# Wattuino-Nanite85_v10.net
KiCad netlist of a schematic drawn in EAGLE
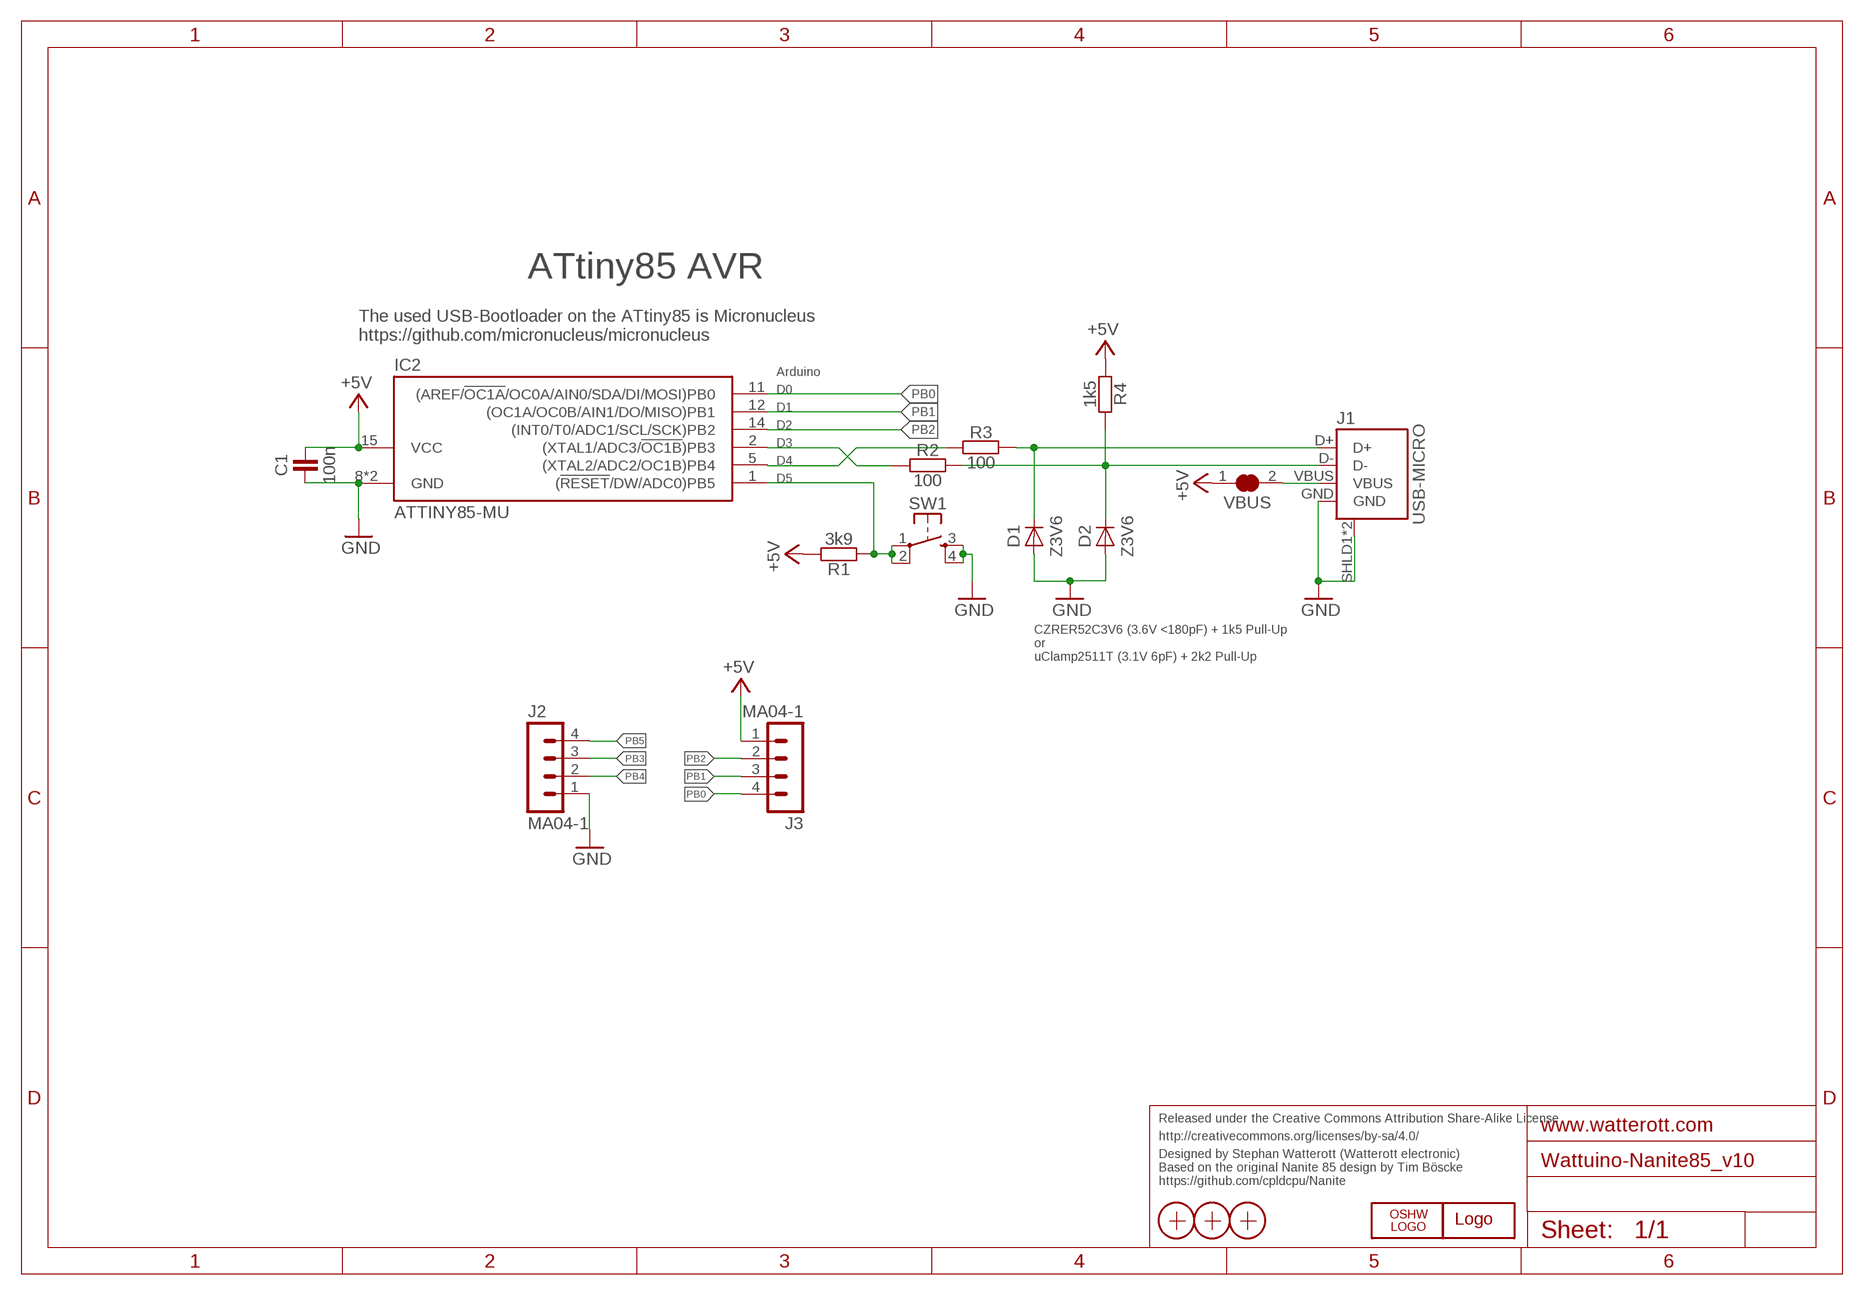
[diagram p0: schematic, sheet 1]

(export (version "E")
  (design (tool "Eeschema 10.0.6"))
  (components
    (comp (ref "C1")
      (value "100n")
      (footprint "eagle-import:C0402")
      (libsource (lib "eagle-import") (part "CAPACITOR-0402"))
    )
    (comp (ref "D1")
      (value "Z3V6")
      (footprint "eagle-import:SOD882")
      (libsource (lib "eagle-import") (part "DIODE-SOD882"))
    )
    (comp (ref "D2")
      (value "Z3V6")
      (footprint "eagle-import:SOD882")
      (libsource (lib "eagle-import") (part "DIODE-SOD882"))
    )
    (comp (ref "IC2")
      (value "ATTINY85-MU")
      (footprint "eagle-import:QFN20-PAD")
      (libsource (lib "eagle-import") (part "ATTINY85-MU"))
    )
    (comp (ref "J1")
      (value "USB-MICRO")
      (footprint "eagle-import:USB-MICRO-10103594")
      (libsource (lib "eagle-import") (part "USB-MICRO"))
    )
    (comp (ref "J2")
      (value "MA04-1")
      (footprint "eagle-import:MA04-1")
      (libsource (lib "eagle-import") (part "MA04-1"))
    )
    (comp (ref "J3")
      (value "MA04-1")
      (footprint "eagle-import:MA04-1")
      (libsource (lib "eagle-import") (part "MA04-1"))
    )
    (comp (ref "LOGO1")
      (value "LOGO-S_PLACE_S")
      (footprint "eagle-import:SPARK_TPLACE_S")
      (libsource (lib "eagle-import") (part "LOGO-S_PLACE_S"))
    )
    (comp (ref "LOGO2")
      (value "OSHW_LOGOX0070")
      (footprint "eagle-import:OSHW_6X70")
      (libsource (lib "eagle-import") (part "OSHW_LOGOX0070"))
    )
    (comp (ref "R1")
      (value "3k9")
      (footprint "eagle-import:C0402")
      (libsource (lib "eagle-import") (part "RESISTOR-0402"))
    )
    (comp (ref "R2")
      (value "100")
      (footprint "eagle-import:C0402")
      (libsource (lib "eagle-import") (part "RESISTOR-0402"))
    )
    (comp (ref "R3")
      (value "100")
      (footprint "eagle-import:C0402")
      (libsource (lib "eagle-import") (part "RESISTOR-0402"))
    )
    (comp (ref "R4")
      (value "1k5")
      (footprint "eagle-import:C0402")
      (libsource (lib "eagle-import") (part "RESISTOR-0402"))
    )
    (comp (ref "SW1")
      (value "SW-TACTILE-PTS840P")
      (footprint "eagle-import:SW_PTS840P")
      (libsource (lib "eagle-import") (part "SW-TACTILE-PTS840P"))
    )
    (comp (ref "VBUS")
      (value "JUMPER2-0603-NC")
      (footprint "eagle-import:JUMPER2-0603_NC")
      (libsource (lib "eagle-import") (part "JUMPER2-0603-NC"))
    )
    (comp (ref "X1")
      (value "PASSER-07")
      (footprint "eagle-import:PASSER_07MM")
      (libsource (lib "eagle-import") (part "PASSER-07"))
    )
    (comp (ref "X2")
      (value "PASSER-07")
      (footprint "eagle-import:PASSER_07MM")
      (libsource (lib "eagle-import") (part "PASSER-07"))
    )
    (comp (ref "X3")
      (value "PASSER-07")
      (footprint "eagle-import:PASSER_07MM")
      (libsource (lib "eagle-import") (part "PASSER-07"))
    )
  )
  (nets
    (net (code "1") (name "+5V") (class "Default")
      (node (ref "C1") (pin "2") (pinfunction "2_2") (pintype "passive"))
      (node (ref "IC2") (pin "15") (pinfunction "VCC_15") (pintype "power_in"))
      (node (ref "J3") (pin "1") (pinfunction "1_1") (pintype "passive"))
      (node (ref "R1") (pin "2") (pinfunction "2_2") (pintype "passive"))
      (node (ref "R4") (pin "1") (pinfunction "1_1") (pintype "passive"))
      (node (ref "VBUS") (pin "1") (pinfunction "1_1") (pintype "passive"))
    )
    (net (code "2") (name "GND") (class "Default")
      (node (ref "C1") (pin "1") (pinfunction "1_1") (pintype "passive"))
      (node (ref "D1") (pin "A") (pinfunction "A_A") (pintype "passive"))
      (node (ref "D2") (pin "A") (pinfunction "A_A") (pintype "passive"))
      (node (ref "IC2") (pin "8") (pinfunction "GND_8") (pintype "power_in"))
      (node (ref "IC2") (pin "TP") (pinfunction "GND_TP") (pintype "power_in"))
      (node (ref "J1") (pin "GND") (pinfunction "GND_GND") (pintype "power_in"))
      (node (ref "J1") (pin "SHLD1") (pinfunction "SHIELD_SHLD1") (pintype "passive"))
      (node (ref "J1") (pin "SHLD2") (pinfunction "SHIELD_SHLD2") (pintype "passive"))
      (node (ref "J2") (pin "1") (pinfunction "1_1") (pintype "passive"))
      (node (ref "SW1") (pin "3") (pinfunction "S1_3") (pintype "passive"))
      (node (ref "SW1") (pin "4") (pinfunction "S2_4") (pintype "passive"))
    )
    (net (code "3") (name "Net-(D1-PadC)") (class "Default")
      (node (ref "D1") (pin "C") (pinfunction "C_C") (pintype "passive"))
      (node (ref "J1") (pin "D+") (pinfunction "D+_D+") (pintype "bidirectional"))
      (node (ref "R3") (pin "2") (pinfunction "2_2") (pintype "passive"))
    )
    (net (code "4") (name "Net-(D2-PadC)") (class "Default")
      (node (ref "D2") (pin "C") (pinfunction "C_C") (pintype "passive"))
      (node (ref "J1") (pin "D-") (pinfunction "D-_D-") (pintype "bidirectional"))
      (node (ref "R2") (pin "2") (pinfunction "2_2") (pintype "passive"))
      (node (ref "R4") (pin "2") (pinfunction "2_2") (pintype "passive"))
    )
    (net (code "5") (name "Net-(J1-PadVBUS)") (class "Default")
      (node (ref "J1") (pin "VBUS") (pinfunction "VBUS_VBUS") (pintype "power_in"))
      (node (ref "VBUS") (pin "2") (pinfunction "2_2") (pintype "passive"))
    )
    (net (code "6") (name "PB0") (class "Default")
      (node (ref "IC2") (pin "11") (pinfunction "(AREF/~{OC1A}/OC0A/AIN0/SDA/DI/MOSI)PB0_11") (pintype "bidirectional"))
      (node (ref "J3") (pin "4") (pinfunction "4_4") (pintype "passive"))
    )
    (net (code "7") (name "PB1") (class "Default")
      (node (ref "IC2") (pin "12") (pinfunction "(OC1A/OC0B/AIN1/DO/MISO)PB1_12") (pintype "bidirectional"))
      (node (ref "J3") (pin "3") (pinfunction "3_3") (pintype "passive"))
    )
    (net (code "8") (name "PB2") (class "Default")
      (node (ref "IC2") (pin "14") (pinfunction "(INT0/T0/ADC1/SCL/SCK)PB2_14") (pintype "bidirectional"))
      (node (ref "J3") (pin "2") (pinfunction "2_2") (pintype "passive"))
    )
    (net (code "9") (name "PB3") (class "Default")
      (node (ref "IC2") (pin "2") (pinfunction "(XTAL1/ADC3/~{OC1B})PB3_2") (pintype "bidirectional"))
      (node (ref "J2") (pin "3") (pinfunction "3_3") (pintype "passive"))
      (node (ref "R2") (pin "1") (pinfunction "1_1") (pintype "passive"))
    )
    (net (code "10") (name "PB4") (class "Default")
      (node (ref "IC2") (pin "5") (pinfunction "(XTAL2/ADC2/OC1B)PB4_5") (pintype "bidirectional"))
      (node (ref "J2") (pin "2") (pinfunction "2_2") (pintype "passive"))
      (node (ref "R3") (pin "1") (pinfunction "1_1") (pintype "passive"))
    )
    (net (code "11") (name "PB5") (class "Default")
      (node (ref "IC2") (pin "1") (pinfunction "(~{RESET}/DW/ADC0)PB5_1") (pintype "bidirectional"))
      (node (ref "J2") (pin "4") (pinfunction "4_4") (pintype "passive"))
      (node (ref "R1") (pin "1") (pinfunction "1_1") (pintype "passive"))
      (node (ref "SW1") (pin "1") (pinfunction "P1_1") (pintype "passive"))
      (node (ref "SW1") (pin "2") (pinfunction "P2_2") (pintype "passive"))
    )
  )
)
